# 6coils-1.net
KiCad netlist of a schematic drawn in EasyEDA
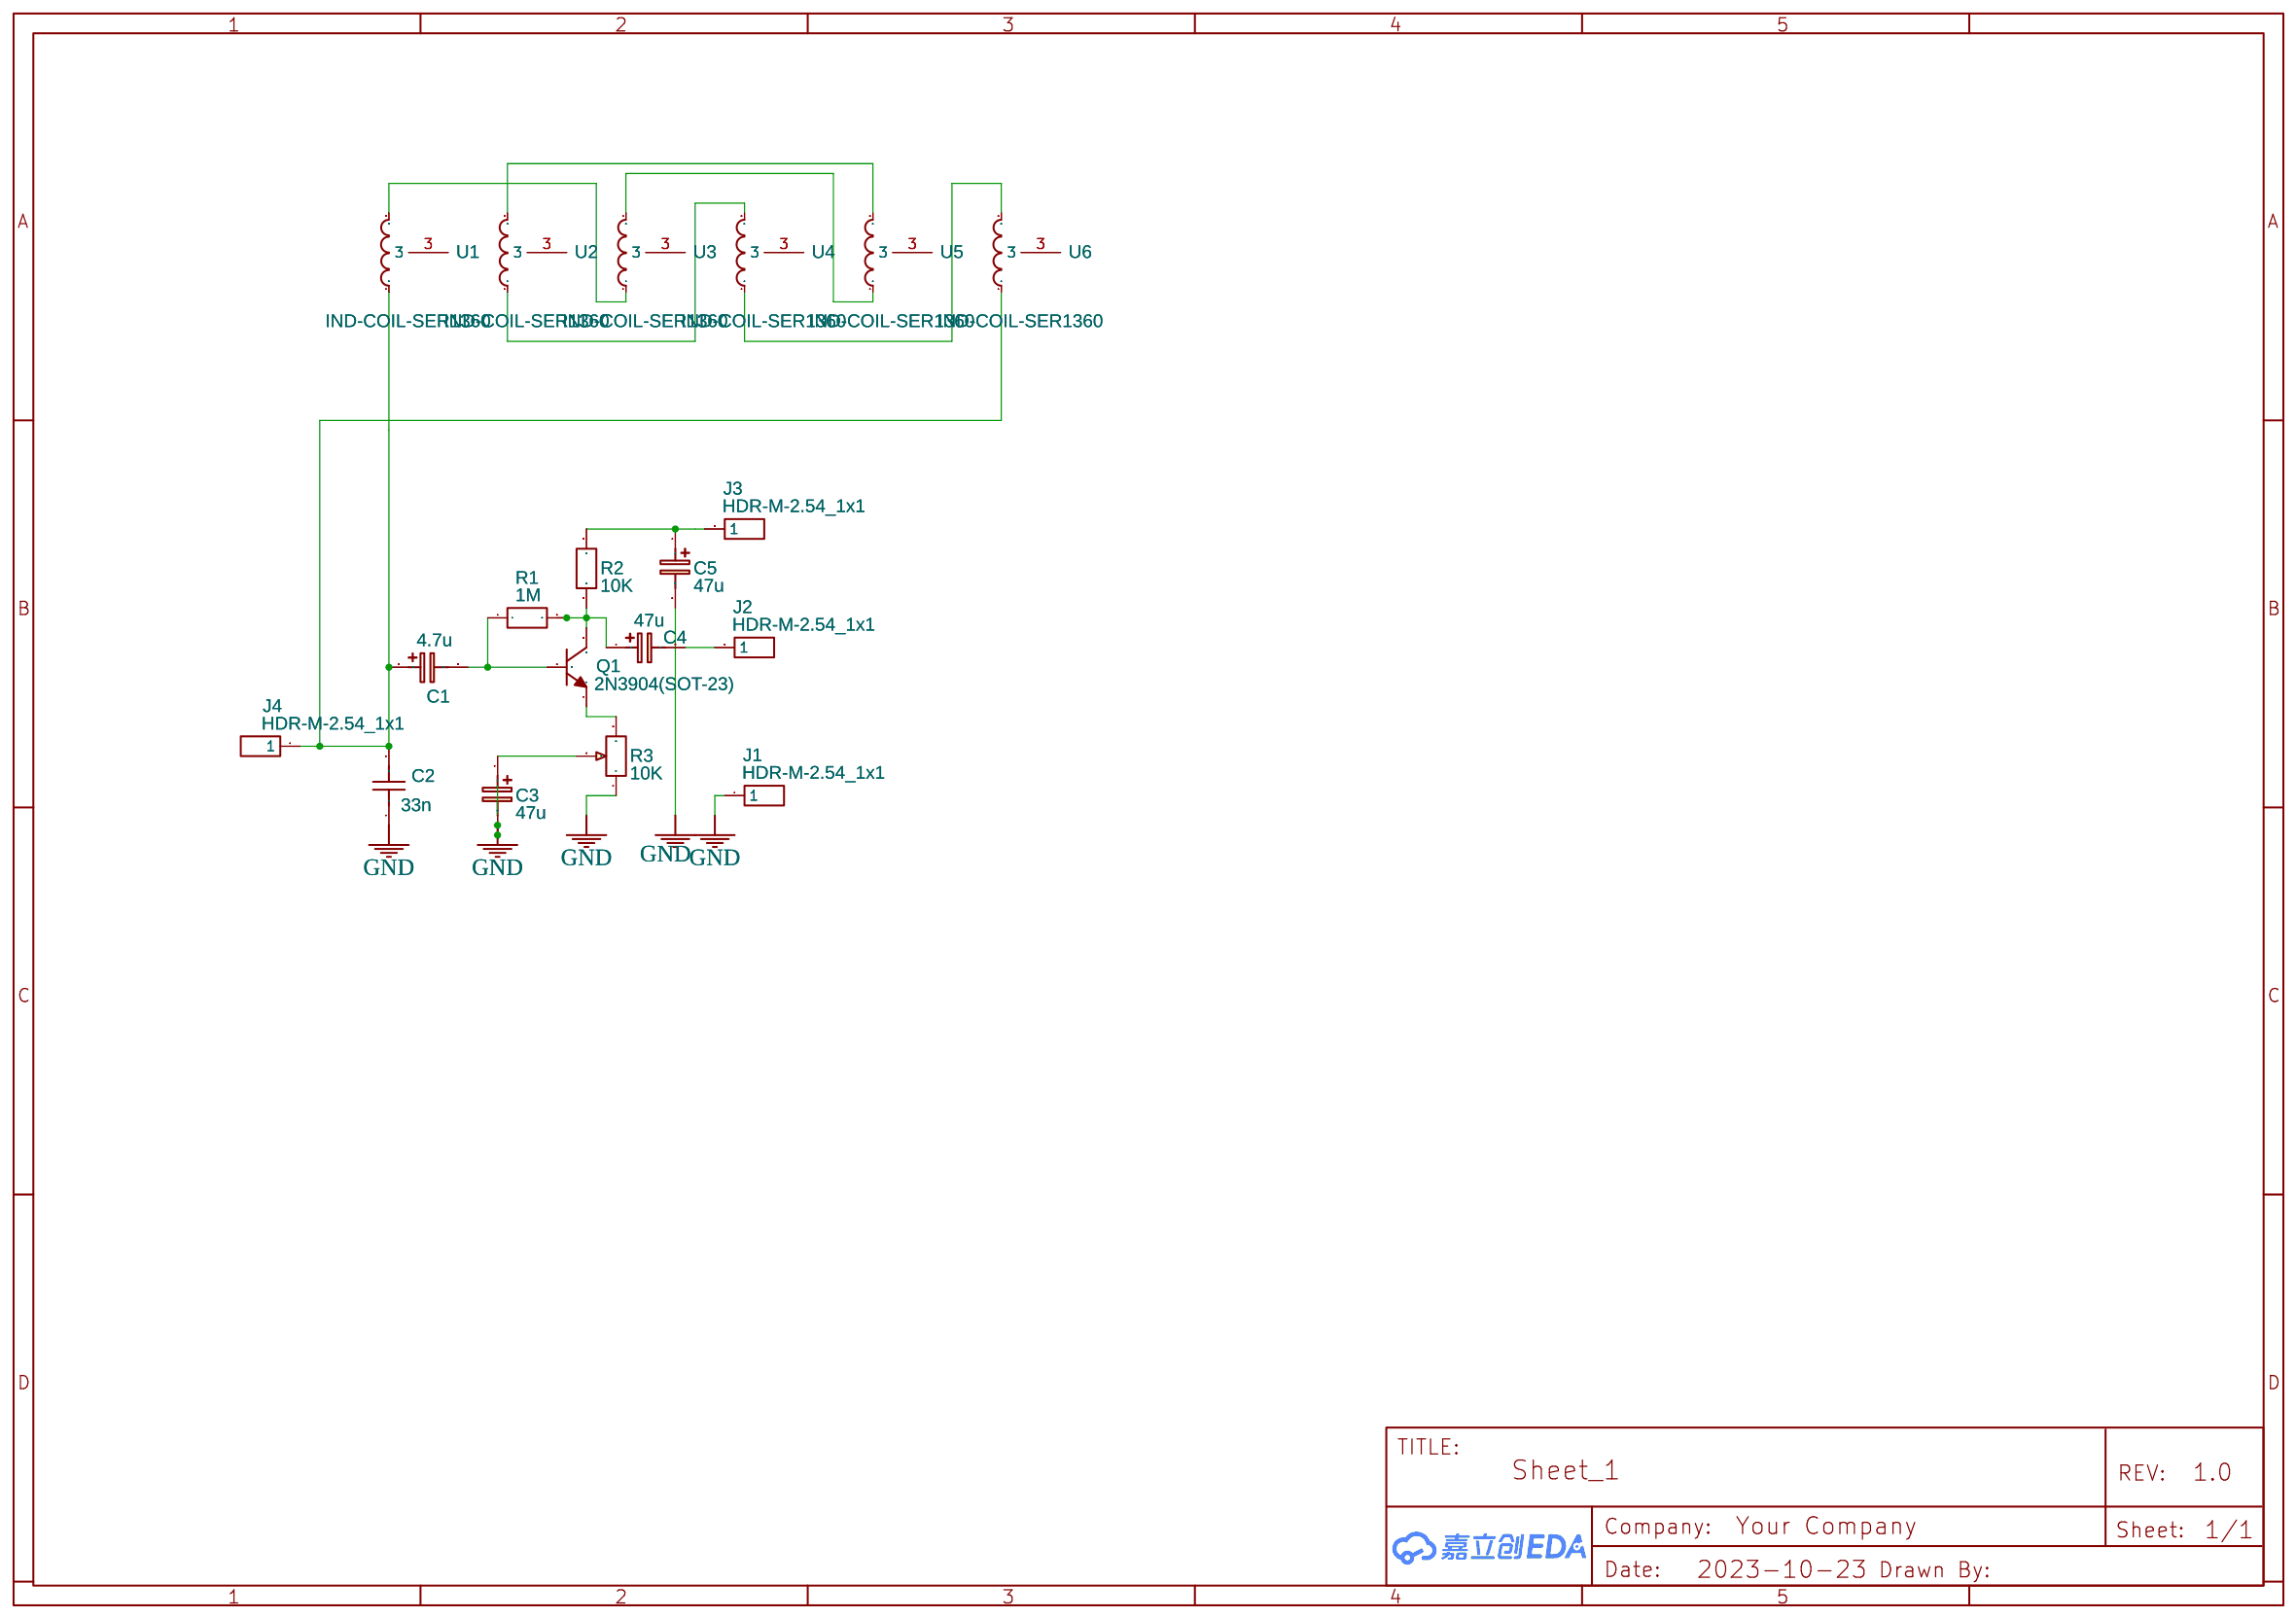
[diagram p0: schematic sheet]

(export (version "E")
  (design (tool "Eeschema 10.0.6"))
  (components
    (comp (ref "C1") (value "4.7u") (libsource (lib "") (part "C_Tan_SMD_A_EU_3")))
    (comp (ref "C2") (value "33n") (libsource (lib "") (part "C_0603_US")))
    (comp (ref "C3") (value "47u") (libsource (lib "") (part "C_Tan_SMD_A_EU")))
    (comp (ref "C4") (value "47u") (libsource (lib "") (part "C_Tan_SMD_A_EU_2")))
    (comp (ref "C5") (value "47u") (libsource (lib "") (part "C_Tan_SMD_A_EU_1")))
    (comp (ref "J1")
      (value "HDR-M-2.54_1x1")
      (fields (field (name "BOM_Supplier Part") "C81276"))
      (libsource (lib "") (part "HDR-M-2.54_1x1"))
    )
    (comp (ref "J2")
      (value "HDR-M-2.54_1x1")
      (fields (field (name "BOM_Supplier Part") "C81276"))
      (libsource (lib "") (part "HDR-M-2.54_1x1"))
    )
    (comp (ref "J3")
      (value "HDR-M-2.54_1x1")
      (fields (field (name "BOM_Supplier Part") "C81276"))
      (libsource (lib "") (part "HDR-M-2.54_1x1"))
    )
    (comp (ref "J4")
      (value "HDR-M-2.54_1x1")
      (fields (field (name "BOM_Supplier Part") "C81276"))
      (libsource (lib "") (part "HDR-M-2.54_1x1_1"))
    )
    (comp (ref "Q1")
      (value "2N3904(SOT-23)")
      (fields
        (field (name "BOM_Manufacturer Part") "2n3904S-RTK/PS")
        (field (name "BOM_Supplier Part") "C18536")
      )
      (libsource (lib "") (part "2N3904(SOT-23)"))
    )
    (comp (ref "R1") (value "1M") (libsource (lib "") (part "R_0603_EU_1")))
    (comp (ref "R2") (value "10K") (libsource (lib "") (part "R_0603_EU")))
    (comp (ref "R3")
      (value "10K")
      (fields (field (name "Manufacturer Part") "RM063-103 10K") (field (name "Manufacturer") "JML"))
      (libsource (lib "") (part "RM063-103 10K"))
    )
    (comp (ref "U1") (value "IND-COIL-SER1360") (libsource (lib "") (part "IND-COIL-SER1360")))
    (comp (ref "U2") (value "IND-COIL-SER1360") (libsource (lib "") (part "IND-COIL-SER1360")))
    (comp (ref "U3") (value "IND-COIL-SER1360") (libsource (lib "") (part "IND-COIL-SER1360")))
    (comp (ref "U4") (value "IND-COIL-SER1360") (libsource (lib "") (part "IND-COIL-SER1360")))
    (comp (ref "U5") (value "IND-COIL-SER1360") (libsource (lib "") (part "IND-COIL-SER1360")))
    (comp (ref "U6") (value "IND-COIL-SER1360") (libsource (lib "") (part "IND-COIL-SER1360")))
  )
  (nets
    (net (code "1") (name "GND") (class "Default")
      (node (ref "C2") (pin "1") (pinfunction "1_1") (pintype "unspecified"))
      (node (ref "C3") (pin "2") (pinfunction "2_2") (pintype "unspecified"))
      (node (ref "C5") (pin "2") (pinfunction "2_2") (pintype "unspecified"))
      (node (ref "J1") (pin "1") (pinfunction "1_1") (pintype "input"))
      (node (ref "R3") (pin "1") (pinfunction "1_1") (pintype "input"))
    )
    (net (code "2") (name "Net-(C1-Pad1)") (class "Default")
      (node (ref "C1") (pin "1") (pinfunction "1_1") (pintype "unspecified"))
      (node (ref "C2") (pin "2") (pinfunction "2_2") (pintype "unspecified"))
      (node (ref "J4") (pin "1") (pinfunction "1_1") (pintype "input"))
      (node (ref "U1") (pin "1") (pinfunction "1_1") (pintype "unspecified"))
      (node (ref "U6") (pin "1") (pinfunction "1_1") (pintype "unspecified"))
    )
    (net (code "3") (name "Net-(C3-Pad1)") (class "Default")
      (node (ref "C3") (pin "1") (pinfunction "1_1") (pintype "unspecified"))
      (node (ref "R3") (pin "2") (pinfunction "2_2") (pintype "input"))
    )
    (net (code "4") (name "Net-(C4-Pad2)") (class "Default")
      (node (ref "C4") (pin "2") (pinfunction "2_2") (pintype "unspecified"))
      (node (ref "J2") (pin "1") (pinfunction "1_1") (pintype "input"))
    )
    (net (code "5") (name "Net-(C5-Pad1)") (class "Default")
      (node (ref "C5") (pin "1") (pinfunction "1_1") (pintype "unspecified"))
      (node (ref "J3") (pin "1") (pinfunction "1_1") (pintype "input"))
      (node (ref "R2") (pin "2") (pinfunction "2_2") (pintype "unspecified"))
    )
    (net (code "6") (name "Net-(Q1-B)") (class "Default")
      (node (ref "C1") (pin "2") (pinfunction "2_2") (pintype "unspecified"))
      (node (ref "Q1") (pin "2") (pinfunction "B_2") (pintype "input"))
      (node (ref "R1") (pin "1") (pinfunction "1_1") (pintype "unspecified"))
    )
    (net (code "7") (name "Net-(Q1-C)") (class "Default")
      (node (ref "C4") (pin "1") (pinfunction "1_1") (pintype "unspecified"))
      (node (ref "Q1") (pin "3") (pinfunction "C_3") (pintype "input"))
      (node (ref "R1") (pin "2") (pinfunction "2_2") (pintype "unspecified"))
      (node (ref "R2") (pin "1") (pinfunction "1_1") (pintype "unspecified"))
    )
    (net (code "8") (name "Net-(Q1-E)") (class "Default")
      (node (ref "Q1") (pin "1") (pinfunction "E_1") (pintype "input"))
      (node (ref "R3") (pin "3") (pinfunction "3_3") (pintype "input"))
    )
    (net (code "9") (name "Net-(U1-Pad2)") (class "Default")
      (node (ref "U1") (pin "2") (pinfunction "2_2") (pintype "unspecified"))
      (node (ref "U3") (pin "1") (pinfunction "1_1") (pintype "unspecified"))
    )
    (net (code "10") (name "Net-(U2-Pad1)") (class "Default")
      (node (ref "U2") (pin "1") (pinfunction "1_1") (pintype "unspecified"))
      (node (ref "U4") (pin "2") (pinfunction "2_2") (pintype "unspecified"))
    )
    (net (code "11") (name "Net-(U2-Pad2)") (class "Default")
      (node (ref "U2") (pin "2") (pinfunction "2_2") (pintype "unspecified"))
      (node (ref "U5") (pin "2") (pinfunction "2_2") (pintype "unspecified"))
    )
    (net (code "12") (name "Net-(U3-Pad2)") (class "Default")
      (node (ref "U3") (pin "2") (pinfunction "2_2") (pintype "unspecified"))
      (node (ref "U5") (pin "1") (pinfunction "1_1") (pintype "unspecified"))
    )
    (net (code "13") (name "Net-(U4-Pad1)") (class "Default")
      (node (ref "U4") (pin "1") (pinfunction "1_1") (pintype "unspecified"))
      (node (ref "U6") (pin "2") (pinfunction "2_2") (pintype "unspecified"))
    )
    (net (code "14") (name "unconnected-(U1-Pad3)") (class "Default")
      (node (ref "U1") (pin "3") (pinfunction "3_3") (pintype "unspecified"))
    )
    (net (code "15") (name "unconnected-(U2-Pad3)") (class "Default")
      (node (ref "U2") (pin "3") (pinfunction "3_3") (pintype "unspecified"))
    )
    (net (code "16") (name "unconnected-(U3-Pad3)") (class "Default")
      (node (ref "U3") (pin "3") (pinfunction "3_3") (pintype "unspecified"))
    )
    (net (code "17") (name "unconnected-(U4-Pad3)") (class "Default")
      (node (ref "U4") (pin "3") (pinfunction "3_3") (pintype "unspecified"))
    )
    (net (code "18") (name "unconnected-(U5-Pad3)") (class "Default")
      (node (ref "U5") (pin "3") (pinfunction "3_3") (pintype "unspecified"))
    )
    (net (code "19") (name "unconnected-(U6-Pad3)") (class "Default")
      (node (ref "U6") (pin "3") (pinfunction "3_3") (pintype "unspecified"))
    )
  )
)
